# Bike_Speedo.net
KiCad netlist of a schematic drawn in EAGLE
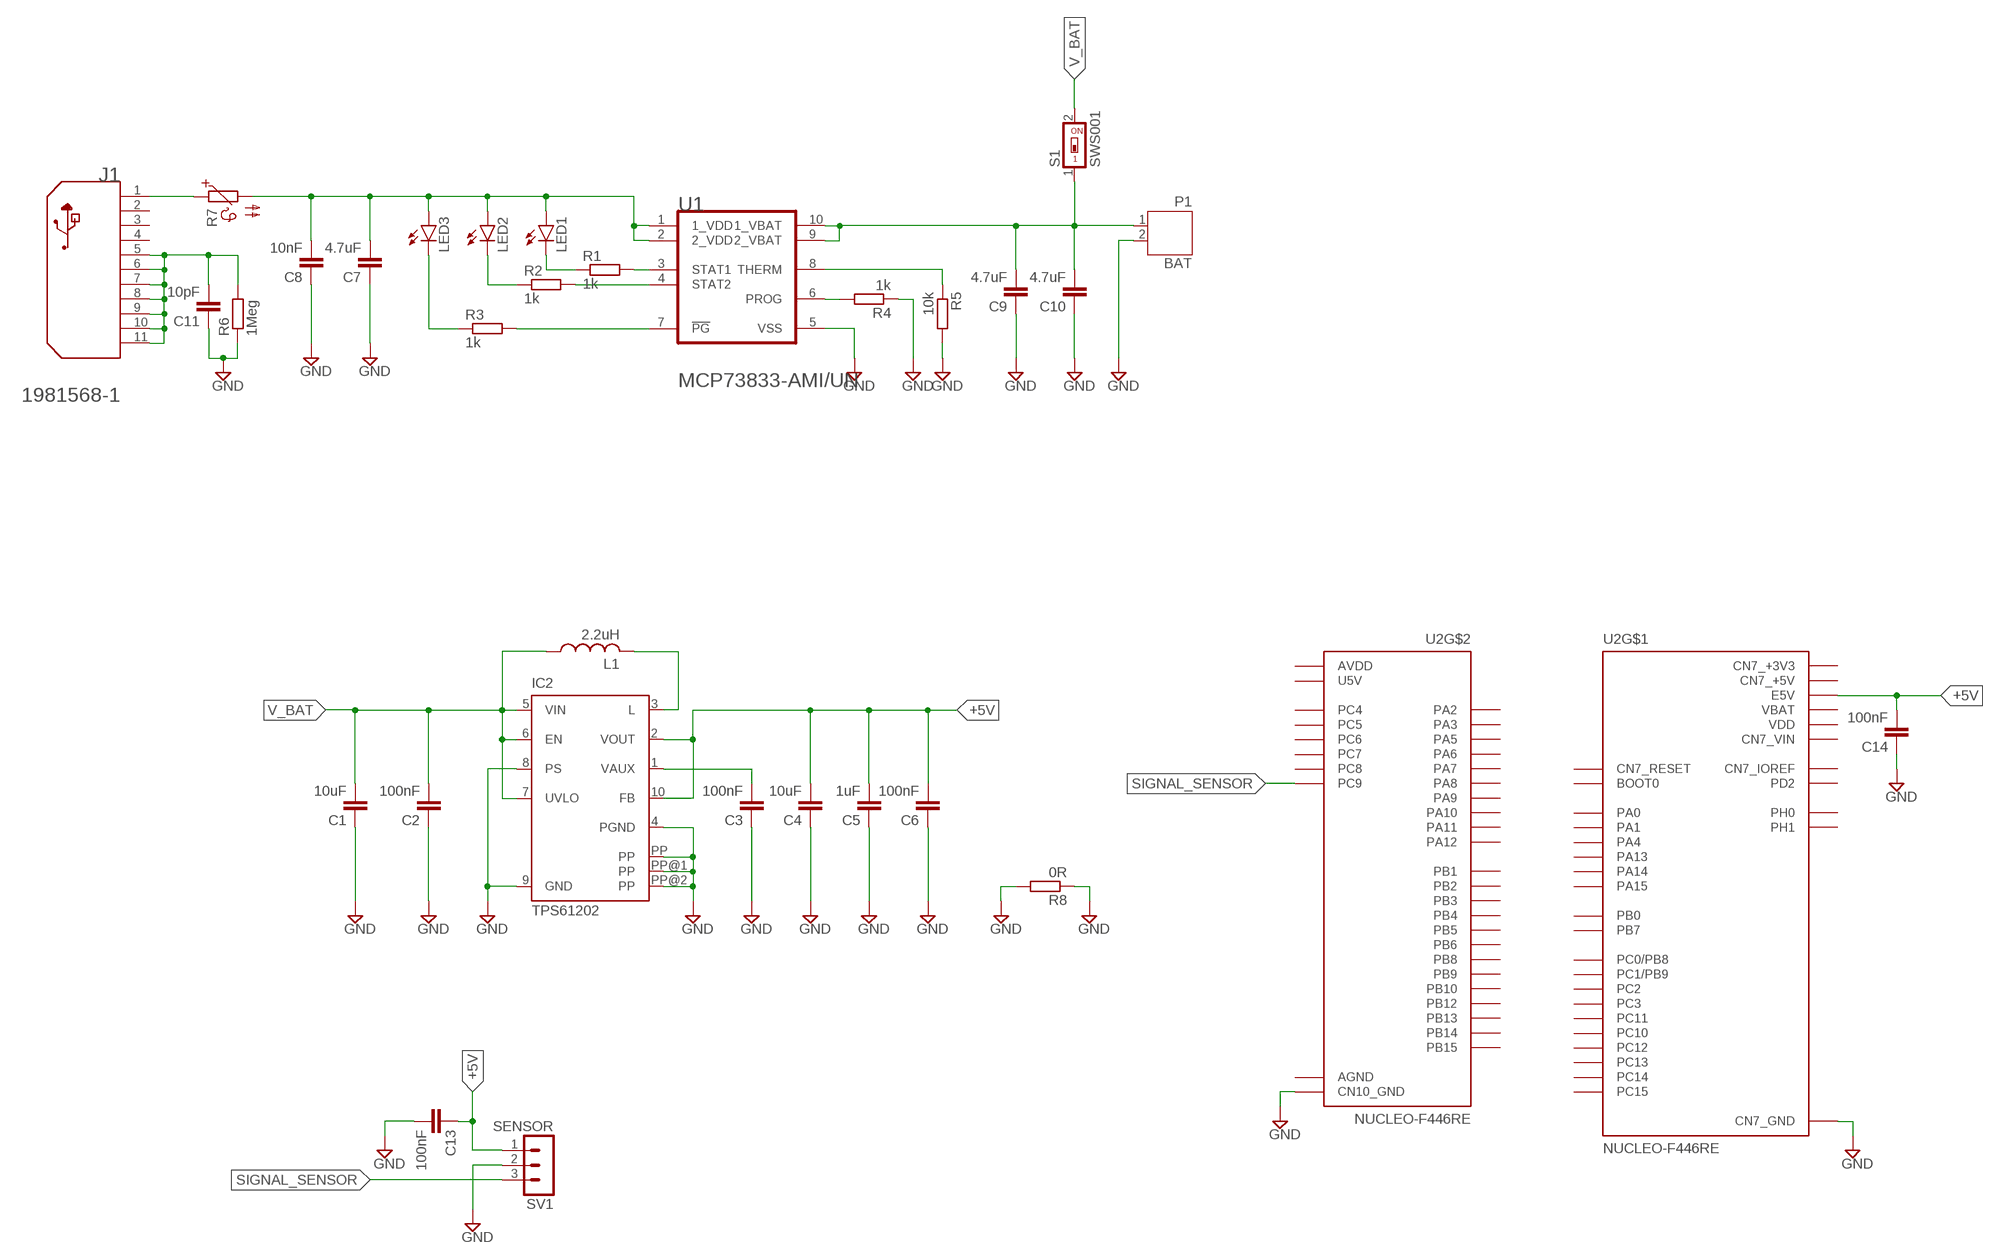
[diagram p0: schematic, sheet 1]

(export (version "E")
  (design (tool "Eeschema 10.0.6"))
  (components
    (comp (ref "C1")
      (value "10uF")
      (footprint "eagle-import:C0805")
      (libsource (lib "eagle-import") (part "C-EUC0805"))
    )
    (comp (ref "C2")
      (value "100nF")
      (footprint "eagle-import:C0805")
      (libsource (lib "eagle-import") (part "C-EUC0805"))
    )
    (comp (ref "C3")
      (value "100nF")
      (footprint "eagle-import:C0805")
      (libsource (lib "eagle-import") (part "C-EUC0805"))
    )
    (comp (ref "C4")
      (value "10uF")
      (footprint "eagle-import:C0805")
      (libsource (lib "eagle-import") (part "C-EUC0805"))
    )
    (comp (ref "C5")
      (value "1uF")
      (footprint "eagle-import:C0805")
      (libsource (lib "eagle-import") (part "C-EUC0805"))
    )
    (comp (ref "C6")
      (value "100nF")
      (footprint "eagle-import:C0805")
      (libsource (lib "eagle-import") (part "C-EUC0805"))
    )
    (comp (ref "C7")
      (value "4.7uF")
      (footprint "eagle-import:C0805")
      (libsource (lib "eagle-import") (part "C-EUC0805"))
    )
    (comp (ref "C8")
      (value "10nF")
      (footprint "eagle-import:C0805")
      (libsource (lib "eagle-import") (part "C-EUC0805"))
    )
    (comp (ref "C9")
      (value "4.7uF")
      (footprint "eagle-import:C0805")
      (libsource (lib "eagle-import") (part "C-EUC0805"))
    )
    (comp (ref "C10")
      (value "4.7uF")
      (footprint "eagle-import:C0805")
      (libsource (lib "eagle-import") (part "C-EUC0805"))
    )
    (comp (ref "C11")
      (value "10pF")
      (footprint "eagle-import:C0805")
      (libsource (lib "eagle-import") (part "C-EUC0805"))
    )
    (comp (ref "C13")
      (value "100nF")
      (footprint "eagle-import:C0805")
      (libsource (lib "eagle-import") (part "C-EUC0805"))
    )
    (comp (ref "C14")
      (value "100nF")
      (footprint "eagle-import:C0805")
      (libsource (lib "eagle-import") (part "C-EUC0805"))
    )
    (comp (ref "IC2")
      (value "TPS61202")
      (footprint "eagle-import:S-PDSO-N10")
      (fields (field (name "MPN") "TPS61202DRCR"))
      (libsource (lib "eagle-import") (part "TPS61202"))
    )
    (comp (ref "J1")
      (value "TE_CONNECTIVITY_1981568-1TE_CONNECTIVITY_1981568-1_0_0")
      (footprint "eagle-import:TE_CONNECTIVITY_1981568-1_0")
      (fields (field (name "MF") "TE Connectivity") (field (name "MPN") "1981568-1"))
      (libsource (lib "eagle-import") (part "TE_CONNECTIVITY_1981568-1TE_CONNECTIVITY_1981568-1_0_0"))
    )
    (comp (ref "L1")
      (value "2.2uH")
      (footprint "eagle-import:L3216C")
      (libsource (lib "eagle-import") (part "L-USL3216C"))
    )
    (comp (ref "LED1")
      (value "LEDSML0805")
      (footprint "eagle-import:SML0805")
      (libsource (lib "eagle-import") (part "LEDSML0805"))
    )
    (comp (ref "LED2")
      (value "LEDSML0805")
      (footprint "eagle-import:SML0805")
      (libsource (lib "eagle-import") (part "LEDSML0805"))
    )
    (comp (ref "LED3")
      (value "LEDSML0805")
      (footprint "eagle-import:SML0805")
      (libsource (lib "eagle-import") (part "LEDSML0805"))
    )
    (comp (ref "P1")
      (value "BAT")
      (footprint "eagle-import:JST-PH2")
      (libsource (lib "eagle-import") (part "JST-PH2"))
    )
    (comp (ref "R1")
      (value "1k")
      (footprint "eagle-import:R0805")
      (libsource (lib "eagle-import") (part "R-EU_R0805"))
    )
    (comp (ref "R2")
      (value "1k")
      (footprint "eagle-import:R0805")
      (libsource (lib "eagle-import") (part "R-EU_R0805"))
    )
    (comp (ref "R3")
      (value "1k")
      (footprint "eagle-import:R0805")
      (libsource (lib "eagle-import") (part "R-EU_R0805"))
    )
    (comp (ref "R4")
      (value "1k")
      (footprint "eagle-import:R0805")
      (libsource (lib "eagle-import") (part "R-EU_R0805"))
    )
    (comp (ref "R5")
      (value "10k")
      (footprint "eagle-import:R0805")
      (libsource (lib "eagle-import") (part "R-EU_R0805"))
    )
    (comp (ref "R6")
      (value "1Meg")
      (footprint "eagle-import:R0805")
      (libsource (lib "eagle-import") (part "R-EU_R0805"))
    )
    (comp (ref "R7")
      (value "PTC660")
      (footprint "eagle-import:P660")
      (libsource (lib "eagle-import") (part "PTC660"))
    )
    (comp (ref "R8")
      (value "0R")
      (footprint "eagle-import:R0805")
      (libsource (lib "eagle-import") (part "R-EU_R0805"))
    )
    (comp (ref "S1")
      (value "SWS001")
      (footprint "eagle-import:SMS-001")
      (libsource (lib "eagle-import") (part "SWS001"))
    )
    (comp (ref "SV1")
      (value "SENSOR")
      (footprint "eagle-import:MA03-1")
      (libsource (lib "eagle-import") (part "MA03-1"))
    )
    (comp (ref "U1")
      (value "MICROCHIP_MCP73833-AMI-UNMICROCHIP_MCP73833-AMI-UN_0_0")
      (footprint "eagle-import:MICROCHIP_MCP73833-AMI-UN_0")
      (fields (field (name "MF") "Microchip") (field (name "MPN") "MCP73833-AMI/UN"))
      (libsource (lib "eagle-import") (part "MICROCHIP_MCP73833-AMI-UNMICROCHIP_MCP73833-AMI-UN_0_0"))
    )
    (comp (ref "U2")
      (value "NUCLEO-F446RE")
      (footprint "eagle-import:MODULE_NUCLEO-F446RE")
      (fields (field (name "MF") "STMicroelectronics"))
      (libsource (lib "eagle-import") (part "NUCLEO-F446RE"))
    )
  )
  (nets
    (net (code "1") (name "+5V") (class "Default")
      (node (ref "C13") (pin "1") (pinfunction "1_1") (pintype "passive"))
      (node (ref "C14") (pin "2") (pinfunction "2_2") (pintype "passive"))
      (node (ref "C4") (pin "2") (pinfunction "2_2") (pintype "passive"))
      (node (ref "C5") (pin "2") (pinfunction "2_2") (pintype "passive"))
      (node (ref "C6") (pin "2") (pinfunction "2_2") (pintype "passive"))
      (node (ref "IC2") (pin "10") (pinfunction "FB_10") (pintype "input"))
      (node (ref "IC2") (pin "2") (pinfunction "VOUT_2") (pintype "passive"))
      (node (ref "SV1") (pin "1") (pinfunction "1_1") (pintype "passive"))
      (node (ref "U2") (pin "CN7_6") (pinfunction "E5V_CN7_6") (pintype "power_in"))
    )
    (net (code "2") (name "/AGND") (class "Default")
      (node (ref "U2") (pin "CN10_32") (pinfunction "AGND_CN10_32") (pintype "power_in"))
    )
    (net (code "3") (name "/AVDD") (class "Default")
      (node (ref "U2") (pin "CN10_7") (pinfunction "AVDD_CN10_7") (pintype "power_in"))
    )
    (net (code "4") (name "/CN7_+3V3") (class "Default")
      (node (ref "U2") (pin "CN7_16") (pinfunction "CN7_+3V3_CN7_16") (pintype "power_in"))
    )
    (net (code "5") (name "/CN7_+5V") (class "Default")
      (node (ref "U2") (pin "CN7_18") (pinfunction "CN7_+5V_CN7_18") (pintype "power_in"))
    )
    (net (code "6") (name "/CN7_VIN") (class "Default")
      (node (ref "U2") (pin "CN7_24") (pinfunction "CN7_VIN_CN7_24") (pintype "power_in"))
    )
    (net (code "7") (name "/U5V") (class "Default")
      (node (ref "U2") (pin "CN10_8") (pinfunction "U5V_CN10_8") (pintype "power_in"))
    )
    (net (code "8") (name "/VBAT") (class "Default")
      (node (ref "U2") (pin "CN7_33") (pinfunction "VBAT_CN7_33") (pintype "power_in"))
    )
    (net (code "9") (name "/VDD") (class "Default")
      (node (ref "U2") (pin "CN7_5") (pinfunction "VDD_CN7_5") (pintype "power_in"))
    )
    (net (code "10") (name "GND") (class "Default")
      (node (ref "C1") (pin "1") (pinfunction "1_1") (pintype "passive"))
      (node (ref "C10") (pin "1") (pinfunction "1_1") (pintype "passive"))
      (node (ref "C11") (pin "1") (pinfunction "1_1") (pintype "passive"))
      (node (ref "C13") (pin "2") (pinfunction "2_2") (pintype "passive"))
      (node (ref "C14") (pin "1") (pinfunction "1_1") (pintype "passive"))
      (node (ref "C2") (pin "1") (pinfunction "1_1") (pintype "passive"))
      (node (ref "C3") (pin "1") (pinfunction "1_1") (pintype "passive"))
      (node (ref "C4") (pin "1") (pinfunction "1_1") (pintype "passive"))
      (node (ref "C5") (pin "1") (pinfunction "1_1") (pintype "passive"))
      (node (ref "C6") (pin "1") (pinfunction "1_1") (pintype "passive"))
      (node (ref "C7") (pin "1") (pinfunction "1_1") (pintype "passive"))
      (node (ref "C8") (pin "1") (pinfunction "1_1") (pintype "passive"))
      (node (ref "C9") (pin "1") (pinfunction "1_1") (pintype "passive"))
      (node (ref "IC2") (pin "4") (pinfunction "PGND_4") (pintype "power_in"))
      (node (ref "IC2") (pin "8") (pinfunction "PS_8") (pintype "input"))
      (node (ref "IC2") (pin "9") (pinfunction "GND_9") (pintype "power_in"))
      (node (ref "IC2") (pin "PP") (pinfunction "PP_PP") (pintype "power_in"))
      (node (ref "IC2") (pin "PP@1") (pinfunction "PP_PP@1") (pintype "power_in"))
      (node (ref "IC2") (pin "PP@2") (pinfunction "PP_PP@2") (pintype "power_in"))
      (node (ref "P1") (pin "2") (pinfunction "2_2") (pintype "passive"))
      (node (ref "R4") (pin "1") (pinfunction "1_1") (pintype "passive"))
      (node (ref "R5") (pin "2") (pinfunction "2_2") (pintype "passive"))
      (node (ref "R6") (pin "1") (pinfunction "1_1") (pintype "passive"))
      (node (ref "R8") (pin "1") (pinfunction "1_1") (pintype "passive"))
      (node (ref "R8") (pin "2") (pinfunction "2_2") (pintype "passive"))
      (node (ref "SV1") (pin "2") (pinfunction "2_2") (pintype "passive"))
      (node (ref "U1") (pin "5") (pinfunction "VSS_5") (pintype "power_in"))
      (node (ref "U2") (pin "CN10_20") (pinfunction "CN10_GND_CN10_20") (pintype "power_in"))
      (node (ref "U2") (pin "CN10_9") (pinfunction "CN10_GND_CN10_9") (pintype "power_in"))
      (node (ref "U2") (pin "CN7_19") (pinfunction "CN7_GND_CN7_19") (pintype "power_in"))
      (node (ref "U2") (pin "CN7_20") (pinfunction "CN7_GND_CN7_20") (pintype "power_in"))
      (node (ref "U2") (pin "CN7_22") (pinfunction "CN7_GND_CN7_22") (pintype "power_in"))
      (node (ref "U2") (pin "CN7_8") (pinfunction "CN7_GND_CN7_8") (pintype "power_in"))
    )
    (net (code "11") (name "Net-(IC2-L)") (class "Default")
      (node (ref "IC2") (pin "3") (pinfunction "L_3") (pintype "input"))
      (node (ref "L1") (pin "2") (pinfunction "2_2") (pintype "passive"))
    )
    (net (code "12") (name "Net-(IC2-VAUX)") (class "Default")
      (node (ref "C3") (pin "2") (pinfunction "2_2") (pintype "passive"))
      (node (ref "IC2") (pin "1") (pinfunction "VAUX_1") (pintype "bidirectional"))
    )
    (net (code "13") (name "Net-(J1-GND)") (class "Default")
      (node (ref "C11") (pin "2") (pinfunction "2_2") (pintype "passive"))
      (node (ref "J1") (pin "10") (pinfunction "SHLD5_10") (pintype "passive"))
      (node (ref "J1") (pin "11") (pinfunction "SHLD6_11") (pintype "passive"))
      (node (ref "J1") (pin "5") (pinfunction "GND_5") (pintype "passive"))
      (node (ref "J1") (pin "6") (pinfunction "SHLD1_6") (pintype "passive"))
      (node (ref "J1") (pin "7") (pinfunction "SHLD2_7") (pintype "passive"))
      (node (ref "J1") (pin "8") (pinfunction "SHLD3_8") (pintype "passive"))
      (node (ref "J1") (pin "9") (pinfunction "SHLD4_9") (pintype "passive"))
      (node (ref "R6") (pin "2") (pinfunction "2_2") (pintype "passive"))
    )
    (net (code "14") (name "Net-(J1-VBUS)") (class "Default")
      (node (ref "J1") (pin "1") (pinfunction "VBUS_1") (pintype "passive"))
      (node (ref "R7") (pin "1") (pinfunction "1_1") (pintype "passive"))
    )
    (net (code "15") (name "Net-(LED1-PadC)") (class "Default")
      (node (ref "LED1") (pin "C") (pinfunction "C_C") (pintype "passive"))
      (node (ref "R1") (pin "1") (pinfunction "1_1") (pintype "passive"))
    )
    (net (code "16") (name "Net-(LED2-PadC)") (class "Default")
      (node (ref "LED2") (pin "C") (pinfunction "C_C") (pintype "passive"))
      (node (ref "R2") (pin "1") (pinfunction "1_1") (pintype "passive"))
    )
    (net (code "17") (name "Net-(LED3-PadC)") (class "Default")
      (node (ref "LED3") (pin "C") (pinfunction "C_C") (pintype "passive"))
      (node (ref "R3") (pin "1") (pinfunction "1_1") (pintype "passive"))
    )
    (net (code "18") (name "Net-(U1-1_VBAT)") (class "Default")
      (node (ref "C10") (pin "2") (pinfunction "2_2") (pintype "passive"))
      (node (ref "C9") (pin "2") (pinfunction "2_2") (pintype "passive"))
      (node (ref "P1") (pin "1") (pinfunction "1_1") (pintype "passive"))
      (node (ref "S1") (pin "1") (pinfunction "1_1") (pintype "passive"))
      (node (ref "U1") (pin "10") (pinfunction "1_VBAT_10") (pintype "power_in"))
      (node (ref "U1") (pin "9") (pinfunction "2_VBAT_9") (pintype "power_in"))
    )
    (net (code "19") (name "Net-(U1-1_VDD)") (class "Default")
      (node (ref "C7") (pin "2") (pinfunction "2_2") (pintype "passive"))
      (node (ref "C8") (pin "2") (pinfunction "2_2") (pintype "passive"))
      (node (ref "LED1") (pin "A") (pinfunction "A_A") (pintype "passive"))
      (node (ref "LED2") (pin "A") (pinfunction "A_A") (pintype "passive"))
      (node (ref "LED3") (pin "A") (pinfunction "A_A") (pintype "passive"))
      (node (ref "R7") (pin "2") (pinfunction "2_2") (pintype "passive"))
      (node (ref "U1") (pin "1") (pinfunction "1_VDD_1") (pintype "power_in"))
      (node (ref "U1") (pin "2") (pinfunction "2_VDD_2") (pintype "power_in"))
    )
    (net (code "20") (name "Net-(U1-PROG)") (class "Default")
      (node (ref "R4") (pin "2") (pinfunction "2_2") (pintype "passive"))
      (node (ref "U1") (pin "6") (pinfunction "PROG_6") (pintype "input"))
    )
    (net (code "21") (name "Net-(U1-STAT1)") (class "Default")
      (node (ref "R1") (pin "2") (pinfunction "2_2") (pintype "passive"))
      (node (ref "U1") (pin "3") (pinfunction "STAT1_3") (pintype "open_collector"))
    )
    (net (code "22") (name "Net-(U1-STAT2)") (class "Default")
      (node (ref "R2") (pin "2") (pinfunction "2_2") (pintype "passive"))
      (node (ref "U1") (pin "4") (pinfunction "STAT2_4") (pintype "open_collector"))
    )
    (net (code "23") (name "Net-(U1-THERM)") (class "Default")
      (node (ref "R5") (pin "1") (pinfunction "1_1") (pintype "passive"))
      (node (ref "U1") (pin "8") (pinfunction "THERM_8") (pintype "input"))
    )
    (net (code "24") (name "Net-(U1-~{PG})") (class "Default")
      (node (ref "R3") (pin "2") (pinfunction "2_2") (pintype "passive"))
      (node (ref "U1") (pin "7") (pinfunction "~{PG}_7") (pintype "open_collector"))
    )
    (net (code "25") (name "SIGNAL_SENSOR") (class "Default")
      (node (ref "SV1") (pin "3") (pinfunction "3_3") (pintype "passive"))
      (node (ref "U2") (pin "CN10_1") (pinfunction "PC9_CN10_1") (pintype "bidirectional"))
    )
    (net (code "26") (name "V_BAT") (class "Default")
      (node (ref "C1") (pin "2") (pinfunction "2_2") (pintype "passive"))
      (node (ref "C2") (pin "2") (pinfunction "2_2") (pintype "passive"))
      (node (ref "IC2") (pin "5") (pinfunction "VIN_5") (pintype "input"))
      (node (ref "IC2") (pin "6") (pinfunction "EN_6") (pintype "input"))
      (node (ref "IC2") (pin "7") (pinfunction "UVLO_7") (pintype "input"))
      (node (ref "L1") (pin "1") (pinfunction "1_1") (pintype "passive"))
      (node (ref "S1") (pin "2") (pinfunction "2_2") (pintype "passive"))
    )
    (net (code "27") (name "unconnected-(J1-D+-Pad3)") (class "Default")
      (node (ref "J1") (pin "3") (pinfunction "D+_3") (pintype "passive"))
    )
    (net (code "28") (name "unconnected-(J1-D--Pad2)") (class "Default")
      (node (ref "J1") (pin "2") (pinfunction "D-_2") (pintype "passive"))
    )
    (net (code "29") (name "unconnected-(J1-ID-Pad4)") (class "Default")
      (node (ref "J1") (pin "4") (pinfunction "ID_4") (pintype "passive"))
    )
    (net (code "30") (name "unconnected-(U2A-BOOT0-PadCN7_7)") (class "Default")
      (node (ref "U2") (pin "CN7_7") (pinfunction "BOOT0_CN7_7") (pintype "bidirectional"))
    )
    (net (code "31") (name "unconnected-(U2A-CN7_IOREF-PadCN7_12)") (class "Default")
      (node (ref "U2") (pin "CN7_12") (pinfunction "CN7_IOREF_CN7_12") (pintype "bidirectional"))
    )
    (net (code "32") (name "unconnected-(U2A-CN7_RESET-PadCN7_14)") (class "Default")
      (node (ref "U2") (pin "CN7_14") (pinfunction "CN7_RESET_CN7_14") (pintype "bidirectional"))
    )
    (net (code "33") (name "unconnected-(U2A-PA0-PadCN7_28)") (class "Default")
      (node (ref "U2") (pin "CN7_28") (pinfunction "PA0_CN7_28") (pintype "bidirectional"))
    )
    (net (code "34") (name "unconnected-(U2A-PA1-PadCN7_30)") (class "Default")
      (node (ref "U2") (pin "CN7_30") (pinfunction "PA1_CN7_30") (pintype "bidirectional"))
    )
    (net (code "35") (name "unconnected-(U2A-PA4-PadCN7_32)") (class "Default")
      (node (ref "U2") (pin "CN7_32") (pinfunction "PA4_CN7_32") (pintype "bidirectional"))
    )
    (net (code "36") (name "unconnected-(U2A-PA13-PadCN7_13)") (class "Default")
      (node (ref "U2") (pin "CN7_13") (pinfunction "PA13_CN7_13") (pintype "bidirectional"))
    )
    (net (code "37") (name "unconnected-(U2A-PA14-PadCN7_15)") (class "Default")
      (node (ref "U2") (pin "CN7_15") (pinfunction "PA14_CN7_15") (pintype "bidirectional"))
    )
    (net (code "38") (name "unconnected-(U2A-PA15-PadCN7_17)") (class "Default")
      (node (ref "U2") (pin "CN7_17") (pinfunction "PA15_CN7_17") (pintype "bidirectional"))
    )
    (net (code "39") (name "unconnected-(U2A-PB0-PadCN7_34)") (class "Default")
      (node (ref "U2") (pin "CN7_34") (pinfunction "PB0_CN7_34") (pintype "bidirectional"))
    )
    (net (code "40") (name "unconnected-(U2A-PB7-PadCN7_21)") (class "Default")
      (node (ref "U2") (pin "CN7_21") (pinfunction "PB7_CN7_21") (pintype "bidirectional"))
    )
    (net (code "41") (name "unconnected-(U2A-PC0{slash}PB8-PadCN7_38)") (class "Default")
      (node (ref "U2") (pin "CN7_38") (pinfunction "PC0/PB8_CN7_38") (pintype "bidirectional"))
    )
    (net (code "42") (name "unconnected-(U2A-PC1{slash}PB9-PadCN7_36)") (class "Default")
      (node (ref "U2") (pin "CN7_36") (pinfunction "PC1/PB9_CN7_36") (pintype "bidirectional"))
    )
    (net (code "43") (name "unconnected-(U2A-PC2-PadCN7_35)") (class "Default")
      (node (ref "U2") (pin "CN7_35") (pinfunction "PC2_CN7_35") (pintype "bidirectional"))
    )
    (net (code "44") (name "unconnected-(U2A-PC3-PadCN7_37)") (class "Default")
      (node (ref "U2") (pin "CN7_37") (pinfunction "PC3_CN7_37") (pintype "bidirectional"))
    )
    (net (code "45") (name "unconnected-(U2A-PC10-PadCN7_1)") (class "Default")
      (node (ref "U2") (pin "CN7_1") (pinfunction "PC10_CN7_1") (pintype "bidirectional"))
    )
    (net (code "46") (name "unconnected-(U2A-PC11-PadCN7_2)") (class "Default")
      (node (ref "U2") (pin "CN7_2") (pinfunction "PC11_CN7_2") (pintype "bidirectional"))
    )
    (net (code "47") (name "unconnected-(U2A-PC12-PadCN7_3)") (class "Default")
      (node (ref "U2") (pin "CN7_3") (pinfunction "PC12_CN7_3") (pintype "bidirectional"))
    )
    (net (code "48") (name "unconnected-(U2A-PC13-PadCN7_23)") (class "Default")
      (node (ref "U2") (pin "CN7_23") (pinfunction "PC13_CN7_23") (pintype "bidirectional"))
    )
    (net (code "49") (name "unconnected-(U2A-PC14-PadCN7_25)") (class "Default")
      (node (ref "U2") (pin "CN7_25") (pinfunction "PC14_CN7_25") (pintype "bidirectional"))
    )
    (net (code "50") (name "unconnected-(U2A-PC15-PadCN7_27)") (class "Default")
      (node (ref "U2") (pin "CN7_27") (pinfunction "PC15_CN7_27") (pintype "bidirectional"))
    )
    (net (code "51") (name "unconnected-(U2A-PD2-PadCN7_4)") (class "Default")
      (node (ref "U2") (pin "CN7_4") (pinfunction "PD2_CN7_4") (pintype "bidirectional"))
    )
    (net (code "52") (name "unconnected-(U2A-PH0-PadCN7_29)") (class "Default")
      (node (ref "U2") (pin "CN7_29") (pinfunction "PH0_CN7_29") (pintype "bidirectional"))
    )
    (net (code "53") (name "unconnected-(U2A-PH1-PadCN7_31)") (class "Default")
      (node (ref "U2") (pin "CN7_31") (pinfunction "PH1_CN7_31") (pintype "bidirectional"))
    )
    (net (code "54") (name "unconnected-(U2B-PA2-PadCN10_35)") (class "Default")
      (node (ref "U2") (pin "CN10_35") (pinfunction "PA2_CN10_35") (pintype "bidirectional"))
    )
    (net (code "55") (name "unconnected-(U2B-PA3-PadCN10_37)") (class "Default")
      (node (ref "U2") (pin "CN10_37") (pinfunction "PA3_CN10_37") (pintype "bidirectional"))
    )
    (net (code "56") (name "unconnected-(U2B-PA5-PadCN10_11)") (class "Default")
      (node (ref "U2") (pin "CN10_11") (pinfunction "PA5_CN10_11") (pintype "bidirectional"))
    )
    (net (code "57") (name "unconnected-(U2B-PA6-PadCN10_13)") (class "Default")
      (node (ref "U2") (pin "CN10_13") (pinfunction "PA6_CN10_13") (pintype "bidirectional"))
    )
    (net (code "58") (name "unconnected-(U2B-PA7-PadCN10_15)") (class "Default")
      (node (ref "U2") (pin "CN10_15") (pinfunction "PA7_CN10_15") (pintype "bidirectional"))
    )
    (net (code "59") (name "unconnected-(U2B-PA8-PadCN10_23)") (class "Default")
      (node (ref "U2") (pin "CN10_23") (pinfunction "PA8_CN10_23") (pintype "bidirectional"))
    )
    (net (code "60") (name "unconnected-(U2B-PA9-PadCN10_21)") (class "Default")
      (node (ref "U2") (pin "CN10_21") (pinfunction "PA9_CN10_21") (pintype "bidirectional"))
    )
    (net (code "61") (name "unconnected-(U2B-PA10-PadCN10_33)") (class "Default")
      (node (ref "U2") (pin "CN10_33") (pinfunction "PA10_CN10_33") (pintype "bidirectional"))
    )
    (net (code "62") (name "unconnected-(U2B-PA11-PadCN10_14)") (class "Default")
      (node (ref "U2") (pin "CN10_14") (pinfunction "PA11_CN10_14") (pintype "bidirectional"))
    )
    (net (code "63") (name "unconnected-(U2B-PA12-PadCN10_12)") (class "Default")
      (node (ref "U2") (pin "CN10_12") (pinfunction "PA12_CN10_12") (pintype "bidirectional"))
    )
    (net (code "64") (name "unconnected-(U2B-PB1-PadCN10_24)") (class "Default")
      (node (ref "U2") (pin "CN10_24") (pinfunction "PB1_CN10_24") (pintype "bidirectional"))
    )
    (net (code "65") (name "unconnected-(U2B-PB2-PadCN10_22)") (class "Default")
      (node (ref "U2") (pin "CN10_22") (pinfunction "PB2_CN10_22") (pintype "bidirectional"))
    )
    (net (code "66") (name "unconnected-(U2B-PB3-PadCN10_31)") (class "Default")
      (node (ref "U2") (pin "CN10_31") (pinfunction "PB3_CN10_31") (pintype "bidirectional"))
    )
    (net (code "67") (name "unconnected-(U2B-PB4-PadCN10_27)") (class "Default")
      (node (ref "U2") (pin "CN10_27") (pinfunction "PB4_CN10_27") (pintype "bidirectional"))
    )
    (net (code "68") (name "unconnected-(U2B-PB5-PadCN10_29)") (class "Default")
      (node (ref "U2") (pin "CN10_29") (pinfunction "PB5_CN10_29") (pintype "bidirectional"))
    )
    (net (code "69") (name "unconnected-(U2B-PB6-PadCN10_17)") (class "Default")
      (node (ref "U2") (pin "CN10_17") (pinfunction "PB6_CN10_17") (pintype "bidirectional"))
    )
    (net (code "70") (name "unconnected-(U2B-PB8-PadCN10_3)") (class "Default")
      (node (ref "U2") (pin "CN10_3") (pinfunction "PB8_CN10_3") (pintype "bidirectional"))
    )
    (net (code "71") (name "unconnected-(U2B-PB9-PadCN10_5)") (class "Default")
      (node (ref "U2") (pin "CN10_5") (pinfunction "PB9_CN10_5") (pintype "bidirectional"))
    )
    (net (code "72") (name "unconnected-(U2B-PB10-PadCN10_25)") (class "Default")
      (node (ref "U2") (pin "CN10_25") (pinfunction "PB10_CN10_25") (pintype "bidirectional"))
    )
    (net (code "73") (name "unconnected-(U2B-PB12-PadCN10_16)") (class "Default")
      (node (ref "U2") (pin "CN10_16") (pinfunction "PB12_CN10_16") (pintype "bidirectional"))
    )
    (net (code "74") (name "unconnected-(U2B-PB13-PadCN10_30)") (class "Default")
      (node (ref "U2") (pin "CN10_30") (pinfunction "PB13_CN10_30") (pintype "bidirectional"))
    )
    (net (code "75") (name "unconnected-(U2B-PB14-PadCN10_28)") (class "Default")
      (node (ref "U2") (pin "CN10_28") (pinfunction "PB14_CN10_28") (pintype "bidirectional"))
    )
    (net (code "76") (name "unconnected-(U2B-PB15-PadCN10_26)") (class "Default")
      (node (ref "U2") (pin "CN10_26") (pinfunction "PB15_CN10_26") (pintype "bidirectional"))
    )
    (net (code "77") (name "unconnected-(U2B-PC4-PadCN10_34)") (class "Default")
      (node (ref "U2") (pin "CN10_34") (pinfunction "PC4_CN10_34") (pintype "bidirectional"))
    )
    (net (code "78") (name "unconnected-(U2B-PC5-PadCN10_6)") (class "Default")
      (node (ref "U2") (pin "CN10_6") (pinfunction "PC5_CN10_6") (pintype "bidirectional"))
    )
    (net (code "79") (name "unconnected-(U2B-PC6-PadCN10_4)") (class "Default")
      (node (ref "U2") (pin "CN10_4") (pinfunction "PC6_CN10_4") (pintype "bidirectional"))
    )
    (net (code "80") (name "unconnected-(U2B-PC7-PadCN10_19)") (class "Default")
      (node (ref "U2") (pin "CN10_19") (pinfunction "PC7_CN10_19") (pintype "bidirectional"))
    )
    (net (code "81") (name "unconnected-(U2B-PC8-PadCN10_2)") (class "Default")
      (node (ref "U2") (pin "CN10_2") (pinfunction "PC8_CN10_2") (pintype "bidirectional"))
    )
  )
)
